# temp_sensor_rev1.net
KiCad netlist of a schematic drawn in EAGLE
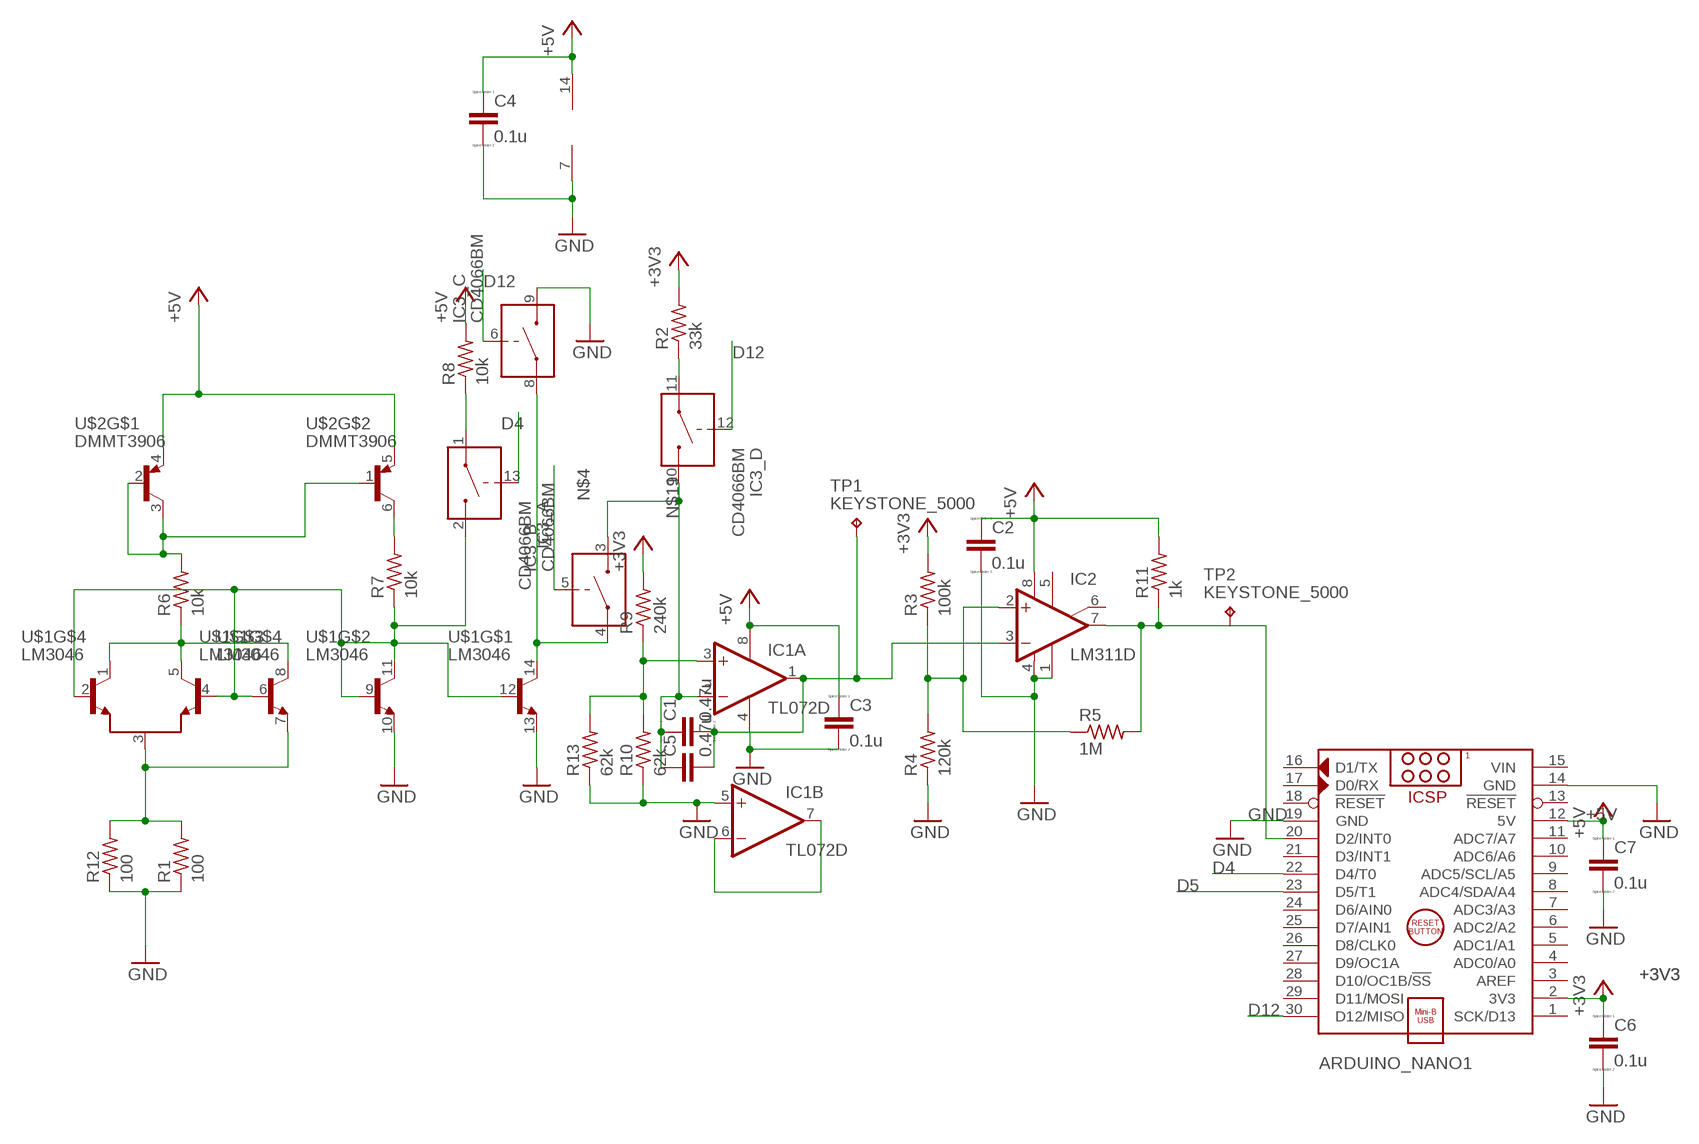
[diagram p0: schematic, sheet 1]

(export (version "E")
  (design (tool "Eeschema 10.0.6"))
  (components
    (comp (ref "ARDUINO_NANO1")
      (value "ARDUINO_NANO")
      (footprint "eagle-import:ARDUINO_NANO")
      (libsource (lib "eagle-import") (part "ARDUINO_NANO"))
    )
    (comp (ref "C1")
      (value "0.47u")
      (footprint "eagle-import:C1206")
      (libsource (lib "eagle-import") (part "CC1206"))
    )
    (comp (ref "C2")
      (value "0.1u")
      (footprint "eagle-import:C0805")
      (libsource (lib "eagle-import") (part "C"))
    )
    (comp (ref "C3")
      (value "0.1u")
      (footprint "eagle-import:C0805")
      (libsource (lib "eagle-import") (part "C"))
    )
    (comp (ref "C4")
      (value "0.1u")
      (footprint "eagle-import:C0805")
      (libsource (lib "eagle-import") (part "C"))
    )
    (comp (ref "C5")
      (value "0.47u")
      (footprint "eagle-import:C2.5-2")
      (libsource (lib "eagle-import") (part "C2.5/2"))
    )
    (comp (ref "C6")
      (value "0.1u")
      (footprint "eagle-import:C0805")
      (libsource (lib "eagle-import") (part "C"))
    )
    (comp (ref "C7")
      (value "0.1u")
      (footprint "eagle-import:C0805")
      (libsource (lib "eagle-import") (part "C"))
    )
    (comp (ref "IC1")
      (value "TL072D")
      (footprint "eagle-import:SO08")
      (libsource (lib "eagle-import") (part "TL072D"))
    )
    (comp (ref "IC2")
      (value "LM311D")
      (footprint "eagle-import:SO08")
      (libsource (lib "eagle-import") (part "LM311D"))
    )
    (comp (ref "IC3")
      (value "CD4066BM")
      (footprint "eagle-import:SO14")
      (libsource (lib "eagle-import") (part "CD4066BM"))
    )
    (comp (ref "R1")
      (value "100")
      (footprint "eagle-import:M1206")
      (libsource (lib "eagle-import") (part "R-US_M1206"))
    )
    (comp (ref "R2")
      (value "33k")
      (footprint "eagle-import:M1206")
      (libsource (lib "eagle-import") (part "R-US_M1206"))
    )
    (comp (ref "R3")
      (value "100k")
      (footprint "eagle-import:M1206")
      (libsource (lib "eagle-import") (part "R-US_M1206"))
    )
    (comp (ref "R4")
      (value "120k")
      (footprint "eagle-import:M1206")
      (libsource (lib "eagle-import") (part "R-US_M1206"))
    )
    (comp (ref "R5")
      (value "1M")
      (footprint "eagle-import:M1206")
      (libsource (lib "eagle-import") (part "R-US_M1206"))
    )
    (comp (ref "R6")
      (value "10k")
      (footprint "eagle-import:M1206")
      (libsource (lib "eagle-import") (part "R-US_M1206"))
    )
    (comp (ref "R7")
      (value "10k")
      (footprint "eagle-import:M1206")
      (libsource (lib "eagle-import") (part "R-US_M1206"))
    )
    (comp (ref "R8")
      (value "10k")
      (footprint "eagle-import:M1206")
      (libsource (lib "eagle-import") (part "R-US_M1206"))
    )
    (comp (ref "R9")
      (value "240k")
      (footprint "eagle-import:M1206")
      (libsource (lib "eagle-import") (part "R-US_M1206"))
    )
    (comp (ref "R10")
      (value "62k")
      (footprint "eagle-import:M1206")
      (libsource (lib "eagle-import") (part "R-US_M1206"))
    )
    (comp (ref "R11")
      (value "1k")
      (footprint "eagle-import:M1206")
      (libsource (lib "eagle-import") (part "R-US_M1206"))
    )
    (comp (ref "R12")
      (value "100")
      (footprint "eagle-import:0207_7")
      (libsource (lib "eagle-import") (part "R-US_0207/7"))
    )
    (comp (ref "R13")
      (value "62k")
      (footprint "eagle-import:0207_7")
      (libsource (lib "eagle-import") (part "R-US_0207/7"))
    )
    (comp (ref "TP1")
      (value "KEYSTONE_5000")
      (footprint "eagle-import:KEYSTONE_5000_MINIATURE")
      (libsource (lib "eagle-import") (part "TESTPOINT"))
    )
    (comp (ref "TP2")
      (value "KEYSTONE_5000")
      (footprint "eagle-import:KEYSTONE_5000_MINIATURE")
      (libsource (lib "eagle-import") (part "TESTPOINT"))
    )
    (comp (ref "U$1")
      (value "LM3046")
      (footprint "eagle-import:SO14")
      (libsource (lib "eagle-import") (part "LM3046"))
    )
    (comp (ref "U$2")
      (value "DMMT3906")
      (footprint "eagle-import:SOT363_PHILIPS")
      (libsource (lib "eagle-import") (part "DMMT3906"))
    )
  )
  (nets
    (net (code "1") (name "+3V3") (class "Default")
      (node (ref "ARDUINO_NANO1") (pin "2") (pinfunction "3V3_2") (pintype "output"))
      (node (ref "C6") (pin "1") (pinfunction "1_1") (pintype "passive"))
      (node (ref "R2") (pin "2") (pinfunction "2_2") (pintype "passive"))
      (node (ref "R3") (pin "2") (pinfunction "2_2") (pintype "passive"))
      (node (ref "R9") (pin "2") (pinfunction "2_2") (pintype "passive"))
    )
    (net (code "2") (name "+5V") (class "Default")
      (node (ref "ARDUINO_NANO1") (pin "12") (pinfunction "5V_12") (pintype "power_in"))
      (node (ref "C2") (pin "1") (pinfunction "1_1") (pintype "passive"))
      (node (ref "C3") (pin "1") (pinfunction "1_1") (pintype "passive"))
      (node (ref "C4") (pin "1") (pinfunction "1_1") (pintype "passive"))
      (node (ref "C7") (pin "1") (pinfunction "1_1") (pintype "passive"))
      (node (ref "IC1") (pin "8") (pinfunction "V+_8") (pintype "power_in"))
      (node (ref "IC2") (pin "8") (pinfunction "V+_8") (pintype "power_in"))
      (node (ref "IC3") (pin "14") (pinfunction "V+_14") (pintype "power_in"))
      (node (ref "R11") (pin "2") (pinfunction "2_2") (pintype "passive"))
      (node (ref "R8") (pin "2") (pinfunction "2_2") (pintype "passive"))
      (node (ref "U$2") (pin "4") (pinfunction "E_4") (pintype "passive"))
      (node (ref "U$2") (pin "5") (pinfunction "E_5") (pintype "passive"))
    )
    (net (code "3") (name "/D4") (class "Default")
      (node (ref "ARDUINO_NANO1") (pin "22") (pinfunction "D4/T0_22") (pintype "bidirectional"))
      (node (ref "IC3") (pin "13") (pinfunction "CONTROL_13") (pintype "bidirectional"))
    )
    (net (code "4") (name "/D5") (class "Default")
      (node (ref "ARDUINO_NANO1") (pin "23") (pinfunction "D5/T1_23") (pintype "bidirectional"))
      (node (ref "IC3") (pin "5") (pinfunction "CONTROL_5") (pintype "bidirectional"))
    )
    (net (code "5") (name "/D12") (class "Default")
      (node (ref "ARDUINO_NANO1") (pin "30") (pinfunction "D12/MISO_30") (pintype "bidirectional"))
      (node (ref "IC3") (pin "12") (pinfunction "CONTROL_12") (pintype "bidirectional"))
      (node (ref "IC3") (pin "6") (pinfunction "CONTROL_6") (pintype "bidirectional"))
    )
    (net (code "6") (name "/N$4") (class "Default")
      (node (ref "IC3") (pin "4") (pinfunction "IN/OUT1_4") (pintype "bidirectional"))
      (node (ref "IC3") (pin "8") (pinfunction "IN/OUT1_8") (pintype "bidirectional"))
      (node (ref "U$1") (pin "14") (pinfunction "C_14") (pintype "passive"))
    )
    (net (code "7") (name "/N$19") (class "Default")
      (node (ref "C1") (pin "1") (pinfunction "1_1") (pintype "passive"))
      (node (ref "C5") (pin "1") (pinfunction "1_1") (pintype "passive"))
      (node (ref "IC1") (pin "2") (pinfunction "-IN_2") (pintype "input"))
      (node (ref "IC3") (pin "10") (pinfunction "IN/OUT2_10") (pintype "bidirectional"))
      (node (ref "IC3") (pin "3") (pinfunction "IN/OUT2_3") (pintype "bidirectional"))
    )
    (net (code "8") (name "/VIN") (class "Default")
      (node (ref "ARDUINO_NANO1") (pin "15") (pinfunction "VIN_15") (pintype "power_in"))
    )
    (net (code "9") (name "GND") (class "Default")
      (node (ref "ARDUINO_NANO1") (pin "14") (pinfunction "GND_14") (pintype "power_in"))
      (node (ref "ARDUINO_NANO1") (pin "19") (pinfunction "GND_19") (pintype "power_in"))
      (node (ref "C2") (pin "2") (pinfunction "2_2") (pintype "passive"))
      (node (ref "C3") (pin "2") (pinfunction "2_2") (pintype "passive"))
      (node (ref "C4") (pin "2") (pinfunction "2_2") (pintype "passive"))
      (node (ref "C6") (pin "2") (pinfunction "2_2") (pintype "passive"))
      (node (ref "C7") (pin "2") (pinfunction "2_2") (pintype "passive"))
      (node (ref "IC1") (pin "4") (pinfunction "V-_4") (pintype "power_in"))
      (node (ref "IC1") (pin "5") (pinfunction "+IN_5") (pintype "input"))
      (node (ref "IC2") (pin "1") (pinfunction "GND_1") (pintype "passive"))
      (node (ref "IC2") (pin "4") (pinfunction "V-_4") (pintype "power_in"))
      (node (ref "IC3") (pin "7") (pinfunction "V-_7") (pintype "power_in"))
      (node (ref "IC3") (pin "9") (pinfunction "IN/OUT2_9") (pintype "bidirectional"))
      (node (ref "R1") (pin "1") (pinfunction "1_1") (pintype "passive"))
      (node (ref "R10") (pin "1") (pinfunction "1_1") (pintype "passive"))
      (node (ref "R12") (pin "1") (pinfunction "1_1") (pintype "passive"))
      (node (ref "R13") (pin "1") (pinfunction "1_1") (pintype "passive"))
      (node (ref "R4") (pin "1") (pinfunction "1_1") (pintype "passive"))
      (node (ref "U$1") (pin "10") (pinfunction "E_10") (pintype "passive"))
      (node (ref "U$1") (pin "13") (pinfunction "E_13") (pintype "passive"))
    )
    (net (code "10") (name "Net-(ARDUINO_NANO1-D2{slash}INT0)") (class "Default")
      (node (ref "ARDUINO_NANO1") (pin "20") (pinfunction "D2/INT0_20") (pintype "bidirectional"))
      (node (ref "IC2") (pin "7") (pinfunction "OUT_7") (pintype "output"))
      (node (ref "R11") (pin "1") (pinfunction "1_1") (pintype "passive"))
      (node (ref "R5") (pin "2") (pinfunction "2_2") (pintype "passive"))
      (node (ref "TP2") (pin "P$1") (pinfunction "P$1_P$1") (pintype "bidirectional"))
    )
    (net (code "11") (name "Net-(IC1A-+IN)") (class "Default")
      (node (ref "IC1") (pin "3") (pinfunction "+IN_3") (pintype "input"))
      (node (ref "R10") (pin "2") (pinfunction "2_2") (pintype "passive"))
      (node (ref "R13") (pin "2") (pinfunction "2_2") (pintype "passive"))
      (node (ref "R9") (pin "1") (pinfunction "1_1") (pintype "passive"))
    )
    (net (code "12") (name "Net-(IC1A-OUT)") (class "Default")
      (node (ref "C1") (pin "2") (pinfunction "2_2") (pintype "passive"))
      (node (ref "C5") (pin "2") (pinfunction "2_2") (pintype "passive"))
      (node (ref "IC1") (pin "1") (pinfunction "OUT_1") (pintype "output"))
      (node (ref "IC2") (pin "3") (pinfunction "-IN_3") (pintype "input"))
      (node (ref "TP1") (pin "P$1") (pinfunction "P$1_P$1") (pintype "bidirectional"))
    )
    (net (code "13") (name "Net-(IC1B--IN)") (class "Default")
      (node (ref "IC1") (pin "6") (pinfunction "-IN_6") (pintype "input"))
      (node (ref "IC1") (pin "7") (pinfunction "OUT_7") (pintype "output"))
    )
    (net (code "14") (name "Net-(IC2-+IN)") (class "Default")
      (node (ref "IC2") (pin "2") (pinfunction "+IN_2") (pintype "input"))
      (node (ref "R3") (pin "1") (pinfunction "1_1") (pintype "passive"))
      (node (ref "R4") (pin "2") (pinfunction "2_2") (pintype "passive"))
      (node (ref "R5") (pin "1") (pinfunction "1_1") (pintype "passive"))
    )
    (net (code "15") (name "Net-(IC3B-IN{slash}OUT1)") (class "Default")
      (node (ref "IC3") (pin "1") (pinfunction "IN/OUT1_1") (pintype "bidirectional"))
      (node (ref "R8") (pin "1") (pinfunction "1_1") (pintype "passive"))
    )
    (net (code "16") (name "Net-(IC3B-IN{slash}OUT2)") (class "Default")
      (node (ref "IC3") (pin "2") (pinfunction "IN/OUT2_2") (pintype "bidirectional"))
      (node (ref "R7") (pin "1") (pinfunction "1_1") (pintype "passive"))
      (node (ref "U$1") (pin "11") (pinfunction "C_11") (pintype "passive"))
      (node (ref "U$1") (pin "12") (pinfunction "B_12") (pintype "passive"))
      (node (ref "U$1") (pin "2") (pinfunction "B_2") (pintype "passive"))
      (node (ref "U$1") (pin "4") (pinfunction "BR_4") (pintype "passive"))
      (node (ref "U$1") (pin "6") (pinfunction "B_6") (pintype "passive"))
      (node (ref "U$1") (pin "9") (pinfunction "B_9") (pintype "passive"))
    )
    (net (code "17") (name "Net-(IC3E-IN{slash}OUT1)") (class "Default")
      (node (ref "IC3") (pin "11") (pinfunction "IN/OUT1_11") (pintype "bidirectional"))
      (node (ref "R2") (pin "1") (pinfunction "1_1") (pintype "passive"))
    )
    (net (code "18") (name "Net-(U$1C-C)") (class "Default")
      (node (ref "R6") (pin "1") (pinfunction "1_1") (pintype "passive"))
      (node (ref "U$1") (pin "1") (pinfunction "C_1") (pintype "passive"))
      (node (ref "U$1") (pin "5") (pinfunction "CR_5") (pintype "passive"))
      (node (ref "U$1") (pin "8") (pinfunction "C_8") (pintype "passive"))
    )
    (net (code "19") (name "Net-(U$1C-E)") (class "Default")
      (node (ref "R1") (pin "2") (pinfunction "2_2") (pintype "passive"))
      (node (ref "R12") (pin "2") (pinfunction "2_2") (pintype "passive"))
      (node (ref "U$1") (pin "3") (pinfunction "E_3") (pintype "passive"))
      (node (ref "U$1") (pin "7") (pinfunction "E_7") (pintype "passive"))
    )
    (net (code "20") (name "Net-(U$2A-B)") (class "Default")
      (node (ref "R6") (pin "2") (pinfunction "2_2") (pintype "passive"))
      (node (ref "U$2") (pin "1") (pinfunction "B_1") (pintype "passive"))
      (node (ref "U$2") (pin "2") (pinfunction "B_2") (pintype "passive"))
      (node (ref "U$2") (pin "3") (pinfunction "C_3") (pintype "passive"))
    )
    (net (code "21") (name "Net-(U$2B-C)") (class "Default")
      (node (ref "R7") (pin "2") (pinfunction "2_2") (pintype "passive"))
      (node (ref "U$2") (pin "6") (pinfunction "C_6") (pintype "passive"))
    )
    (net (code "22") (name "unconnected-(ARDUINO_NANO1-ADC0{slash}A0-Pad4)") (class "Default")
      (node (ref "ARDUINO_NANO1") (pin "4") (pinfunction "ADC0/A0_4") (pintype "bidirectional"))
    )
    (net (code "23") (name "unconnected-(ARDUINO_NANO1-ADC1{slash}A1-Pad5)") (class "Default")
      (node (ref "ARDUINO_NANO1") (pin "5") (pinfunction "ADC1/A1_5") (pintype "bidirectional"))
    )
    (net (code "24") (name "unconnected-(ARDUINO_NANO1-ADC2{slash}A2-Pad6)") (class "Default")
      (node (ref "ARDUINO_NANO1") (pin "6") (pinfunction "ADC2/A2_6") (pintype "bidirectional"))
    )
    (net (code "25") (name "unconnected-(ARDUINO_NANO1-ADC3{slash}A3-Pad7)") (class "Default")
      (node (ref "ARDUINO_NANO1") (pin "7") (pinfunction "ADC3/A3_7") (pintype "bidirectional"))
    )
    (net (code "26") (name "unconnected-(ARDUINO_NANO1-ADC4{slash}SDA{slash}A4-Pad8)") (class "Default")
      (node (ref "ARDUINO_NANO1") (pin "8") (pinfunction "ADC4/SDA/A4_8") (pintype "bidirectional"))
    )
    (net (code "27") (name "unconnected-(ARDUINO_NANO1-ADC5{slash}SCL{slash}A5-Pad9)") (class "Default")
      (node (ref "ARDUINO_NANO1") (pin "9") (pinfunction "ADC5/SCL/A5_9") (pintype "bidirectional"))
    )
    (net (code "28") (name "unconnected-(ARDUINO_NANO1-ADC6{slash}A6-Pad10)") (class "Default")
      (node (ref "ARDUINO_NANO1") (pin "10") (pinfunction "ADC6/A6_10") (pintype "bidirectional"))
    )
    (net (code "29") (name "unconnected-(ARDUINO_NANO1-ADC7{slash}A7-Pad11)") (class "Default")
      (node (ref "ARDUINO_NANO1") (pin "11") (pinfunction "ADC7/A7_11") (pintype "bidirectional"))
    )
    (net (code "30") (name "unconnected-(ARDUINO_NANO1-AREF-Pad3)") (class "Default")
      (node (ref "ARDUINO_NANO1") (pin "3") (pinfunction "AREF_3") (pintype "input"))
    )
    (net (code "31") (name "unconnected-(ARDUINO_NANO1-D0{slash}RX-Pad17)") (class "Default")
      (node (ref "ARDUINO_NANO1") (pin "17") (pinfunction "D0/RX_17") (pintype "bidirectional"))
    )
    (net (code "32") (name "unconnected-(ARDUINO_NANO1-D1{slash}TX-Pad16)") (class "Default")
      (node (ref "ARDUINO_NANO1") (pin "16") (pinfunction "D1/TX_16") (pintype "bidirectional"))
    )
    (net (code "33") (name "unconnected-(ARDUINO_NANO1-D3{slash}INT1-Pad21)") (class "Default")
      (node (ref "ARDUINO_NANO1") (pin "21") (pinfunction "D3/INT1_21") (pintype "bidirectional"))
    )
    (net (code "34") (name "unconnected-(ARDUINO_NANO1-D6{slash}AIN0-Pad24)") (class "Default")
      (node (ref "ARDUINO_NANO1") (pin "24") (pinfunction "D6/AIN0_24") (pintype "bidirectional"))
    )
    (net (code "35") (name "unconnected-(ARDUINO_NANO1-D7{slash}AIN1-Pad25)") (class "Default")
      (node (ref "ARDUINO_NANO1") (pin "25") (pinfunction "D7/AIN1_25") (pintype "bidirectional"))
    )
    (net (code "36") (name "unconnected-(ARDUINO_NANO1-D8{slash}CLK0-Pad26)") (class "Default")
      (node (ref "ARDUINO_NANO1") (pin "26") (pinfunction "D8/CLK0_26") (pintype "bidirectional"))
    )
    (net (code "37") (name "unconnected-(ARDUINO_NANO1-D9{slash}OC1A-Pad27)") (class "Default")
      (node (ref "ARDUINO_NANO1") (pin "27") (pinfunction "D9/OC1A_27") (pintype "bidirectional"))
    )
    (net (code "38") (name "unconnected-(ARDUINO_NANO1-D10{slash}OC1B{slash}~{SS}-Pad28)") (class "Default")
      (node (ref "ARDUINO_NANO1") (pin "28") (pinfunction "D10/OC1B/~{SS}_28") (pintype "bidirectional"))
    )
    (net (code "39") (name "unconnected-(ARDUINO_NANO1-D11{slash}MOSI-Pad29)") (class "Default")
      (node (ref "ARDUINO_NANO1") (pin "29") (pinfunction "D11/MOSI_29") (pintype "bidirectional"))
    )
    (net (code "40") (name "unconnected-(ARDUINO_NANO1-SCK{slash}D13-Pad1)") (class "Default")
      (node (ref "ARDUINO_NANO1") (pin "1") (pinfunction "SCK/D13_1") (pintype "bidirectional"))
    )
    (net (code "41") (name "unconnected-(ARDUINO_NANO1-~{RESET}-Pad13)") (class "Default")
      (node (ref "ARDUINO_NANO1") (pin "13") (pinfunction "~{RESET}_13") (pintype "input"))
    )
    (net (code "42") (name "unconnected-(ARDUINO_NANO1-~{RESET}-Pad18)") (class "Default")
      (node (ref "ARDUINO_NANO1") (pin "18") (pinfunction "~{RESET}_18") (pintype "input"))
    )
    (net (code "43") (name "unconnected-(IC2-ON-Pad5)") (class "Default")
      (node (ref "IC2") (pin "5") (pinfunction "ON_5") (pintype "passive"))
    )
    (net (code "44") (name "unconnected-(IC2-ON{slash}STR-Pad6)") (class "Default")
      (node (ref "IC2") (pin "6") (pinfunction "ON/STR_6") (pintype "passive"))
    )
  )
)
